# sche_LC_FILTER.net
KiCad netlist of a schematic drawn in Altium Designer
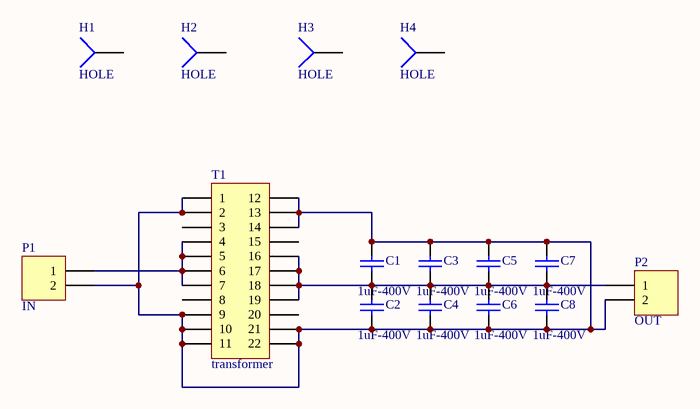
[diagram p0: sche_LC_FILTER.SchDoc]

(export (version "E")
  (design (tool "Eeschema 10.0.6"))
  (components
    (comp (ref "C1")
      (value "1uF-400V")
      (footprint "TU")
      (description "Capacitor")
      (fields (field (name "Comment") "Cap") (field (name "PUBLISHER") "Altium Limited"))
      (libsource (lib "Miscellaneous Devices") (part "Cap"))
    )
    (comp (ref "C2")
      (value "1uF-400V")
      (footprint "TU")
      (description "Capacitor")
      (fields (field (name "Comment") "Cap") (field (name "PUBLISHER") "Altium Limited"))
      (libsource (lib "Miscellaneous Devices") (part "Cap"))
    )
    (comp (ref "C3")
      (value "1uF-400V")
      (footprint "TU")
      (description "Capacitor")
      (fields (field (name "Comment") "Cap") (field (name "PUBLISHER") "Altium Limited"))
      (libsource (lib "Miscellaneous Devices") (part "Cap"))
    )
    (comp (ref "C4")
      (value "1uF-400V")
      (footprint "TU")
      (description "Capacitor")
      (fields (field (name "Comment") "Cap") (field (name "PUBLISHER") "Altium Limited"))
      (libsource (lib "Miscellaneous Devices") (part "Cap"))
    )
    (comp (ref "C5")
      (value "1uF-400V")
      (footprint "TU")
      (description "Capacitor")
      (fields (field (name "Comment") "Cap") (field (name "PUBLISHER") "Altium Limited"))
      (libsource (lib "Miscellaneous Devices") (part "Cap"))
    )
    (comp (ref "C6")
      (value "1uF-400V")
      (footprint "TU")
      (description "Capacitor")
      (fields (field (name "Comment") "Cap") (field (name "PUBLISHER") "Altium Limited"))
      (libsource (lib "Miscellaneous Devices") (part "Cap"))
    )
    (comp (ref "C7")
      (value "1uF-400V")
      (footprint "TU")
      (description "Capacitor")
      (fields (field (name "Comment") "Cap") (field (name "PUBLISHER") "Altium Limited"))
      (libsource (lib "Miscellaneous Devices") (part "Cap"))
    )
    (comp (ref "C8")
      (value "1uF-400V")
      (footprint "TU")
      (description "Capacitor")
      (fields (field (name "Comment") "Cap") (field (name "PUBLISHER") "Altium Limited"))
      (libsource (lib "Miscellaneous Devices") (part "Cap"))
    )
    (comp (ref "H1")
      (value "HOLE")
      (footprint "HOLE")
      (description "Socket")
      (fields (field (name "PUBLISHER") "Altium Limited"))
      (libsource (lib "Miscellaneous Connectors") (part "Socket"))
    )
    (comp (ref "H2")
      (value "HOLE")
      (footprint "HOLE")
      (description "Socket")
      (fields (field (name "PUBLISHER") "Altium Limited"))
      (libsource (lib "Miscellaneous Connectors") (part "Socket"))
    )
    (comp (ref "H3")
      (value "HOLE")
      (footprint "HOLE")
      (description "Socket")
      (fields (field (name "PUBLISHER") "Altium Limited"))
      (libsource (lib "Miscellaneous Connectors") (part "Socket"))
    )
    (comp (ref "H4")
      (value "HOLE")
      (footprint "HOLE")
      (description "Socket")
      (fields (field (name "PUBLISHER") "Altium Limited"))
      (libsource (lib "Miscellaneous Connectors") (part "Socket"))
    )
    (comp (ref "P1")
      (value "IN")
      (footprint "CONNECTOR2")
      (description "Header, 2-Pin")
      (fields (field (name "PUBLISHER") "Altium Limited"))
      (libsource (lib "") (part "Header 2_1"))
    )
    (comp (ref "P2")
      (value "OUT")
      (footprint "CONNECTOR2")
      (description "Header, 2-Pin")
      (fields (field (name "PUBLISHER") "Altium Limited"))
      (libsource (lib "Miscellaneous Connectors") (part "Header 2"))
    )
    (comp (ref "T1")
      (value "transformer")
      (footprint "EER49:PCBComponent_1")
      (description "Header, 11-Pin, Dual row")
      (fields (field (name "PUBLISHER") "Altium Limited"))
      (libsource (lib "Miscellaneous Connectors") (part "Header 11X2A"))
    )
  )
  (nets
    (net (code "1") (name "Net-(C1-Pad1)") (class "Default")
      (node (ref "C1") (pin "1") (pinfunction "1_1") (pintype "passive"))
      (node (ref "C2") (pin "2") (pinfunction "2_2") (pintype "passive"))
      (node (ref "C3") (pin "1") (pinfunction "1_1") (pintype "passive"))
      (node (ref "C4") (pin "2") (pinfunction "2_2") (pintype "passive"))
      (node (ref "C5") (pin "1") (pinfunction "1_1") (pintype "passive"))
      (node (ref "C6") (pin "2") (pinfunction "2_2") (pintype "passive"))
      (node (ref "C7") (pin "1") (pinfunction "1_1") (pintype "passive"))
      (node (ref "C8") (pin "2") (pinfunction "2_2") (pintype "passive"))
      (node (ref "P2") (pin "1") (pinfunction "1_1") (pintype "passive"))
      (node (ref "T1") (pin "16") (pinfunction "16_16") (pintype "passive"))
      (node (ref "T1") (pin "17") (pinfunction "17_17") (pintype "passive"))
      (node (ref "T1") (pin "18") (pinfunction "18_18") (pintype "passive"))
      (node (ref "T1") (pin "19") (pinfunction "19_19") (pintype "passive"))
    )
    (net (code "2") (name "Net-(C1-Pad2)") (class "Default")
      (node (ref "C1") (pin "2") (pinfunction "2_2") (pintype "passive"))
      (node (ref "C2") (pin "1") (pinfunction "1_1") (pintype "passive"))
      (node (ref "C3") (pin "2") (pinfunction "2_2") (pintype "passive"))
      (node (ref "C4") (pin "1") (pinfunction "1_1") (pintype "passive"))
      (node (ref "C5") (pin "2") (pinfunction "2_2") (pintype "passive"))
      (node (ref "C6") (pin "1") (pinfunction "1_1") (pintype "passive"))
      (node (ref "C7") (pin "2") (pinfunction "2_2") (pintype "passive"))
      (node (ref "C8") (pin "1") (pinfunction "1_1") (pintype "passive"))
      (node (ref "P1") (pin "2") (pinfunction "2_2") (pintype "passive"))
      (node (ref "P2") (pin "2") (pinfunction "2_2") (pintype "passive"))
      (node (ref "T1") (pin "1") (pinfunction "1_1") (pintype "passive"))
      (node (ref "T1") (pin "10") (pinfunction "10_10") (pintype "passive"))
      (node (ref "T1") (pin "11") (pinfunction "11_11") (pintype "passive"))
      (node (ref "T1") (pin "12") (pinfunction "12_12") (pintype "passive"))
      (node (ref "T1") (pin "13") (pinfunction "13_13") (pintype "passive"))
      (node (ref "T1") (pin "14") (pinfunction "14_14") (pintype "passive"))
      (node (ref "T1") (pin "2") (pinfunction "2_2") (pintype "passive"))
      (node (ref "T1") (pin "21") (pinfunction "21_21") (pintype "passive"))
      (node (ref "T1") (pin "22") (pinfunction "22_22") (pintype "passive"))
      (node (ref "T1") (pin "9") (pinfunction "9_9") (pintype "passive"))
    )
    (net (code "3") (name "Net-(P1-Pad1)") (class "Default")
      (node (ref "P1") (pin "1") (pinfunction "1_1") (pintype "passive"))
      (node (ref "T1") (pin "4") (pinfunction "4_4") (pintype "passive"))
      (node (ref "T1") (pin "5") (pinfunction "5_5") (pintype "passive"))
      (node (ref "T1") (pin "6") (pinfunction "6_6") (pintype "passive"))
      (node (ref "T1") (pin "7") (pinfunction "7_7") (pintype "passive"))
    )
    (net (code "4") (name "unconnected-(H1-Pad1)") (class "Default")
      (node (ref "H1") (pin "1") (pinfunction "1_1") (pintype "passive"))
    )
    (net (code "5") (name "unconnected-(H2-Pad1)") (class "Default")
      (node (ref "H2") (pin "1") (pinfunction "1_1") (pintype "passive"))
    )
    (net (code "6") (name "unconnected-(H3-Pad1)") (class "Default")
      (node (ref "H3") (pin "1") (pinfunction "1_1") (pintype "passive"))
    )
    (net (code "7") (name "unconnected-(H4-Pad1)") (class "Default")
      (node (ref "H4") (pin "1") (pinfunction "1_1") (pintype "passive"))
    )
    (net (code "8") (name "unconnected-(T1-Pad3)") (class "Default")
      (node (ref "T1") (pin "3") (pinfunction "3_3") (pintype "passive"))
    )
    (net (code "9") (name "unconnected-(T1-Pad8)") (class "Default")
      (node (ref "T1") (pin "8") (pinfunction "8_8") (pintype "passive"))
    )
    (net (code "10") (name "unconnected-(T1-Pad15)") (class "Default")
      (node (ref "T1") (pin "15") (pinfunction "15_15") (pintype "passive"))
    )
    (net (code "11") (name "unconnected-(T1-Pad20)") (class "Default")
      (node (ref "T1") (pin "20") (pinfunction "20_20") (pintype "passive"))
    )
  )
)
